# fsr_array.net
KiCad netlist of a schematic drawn in EAGLE
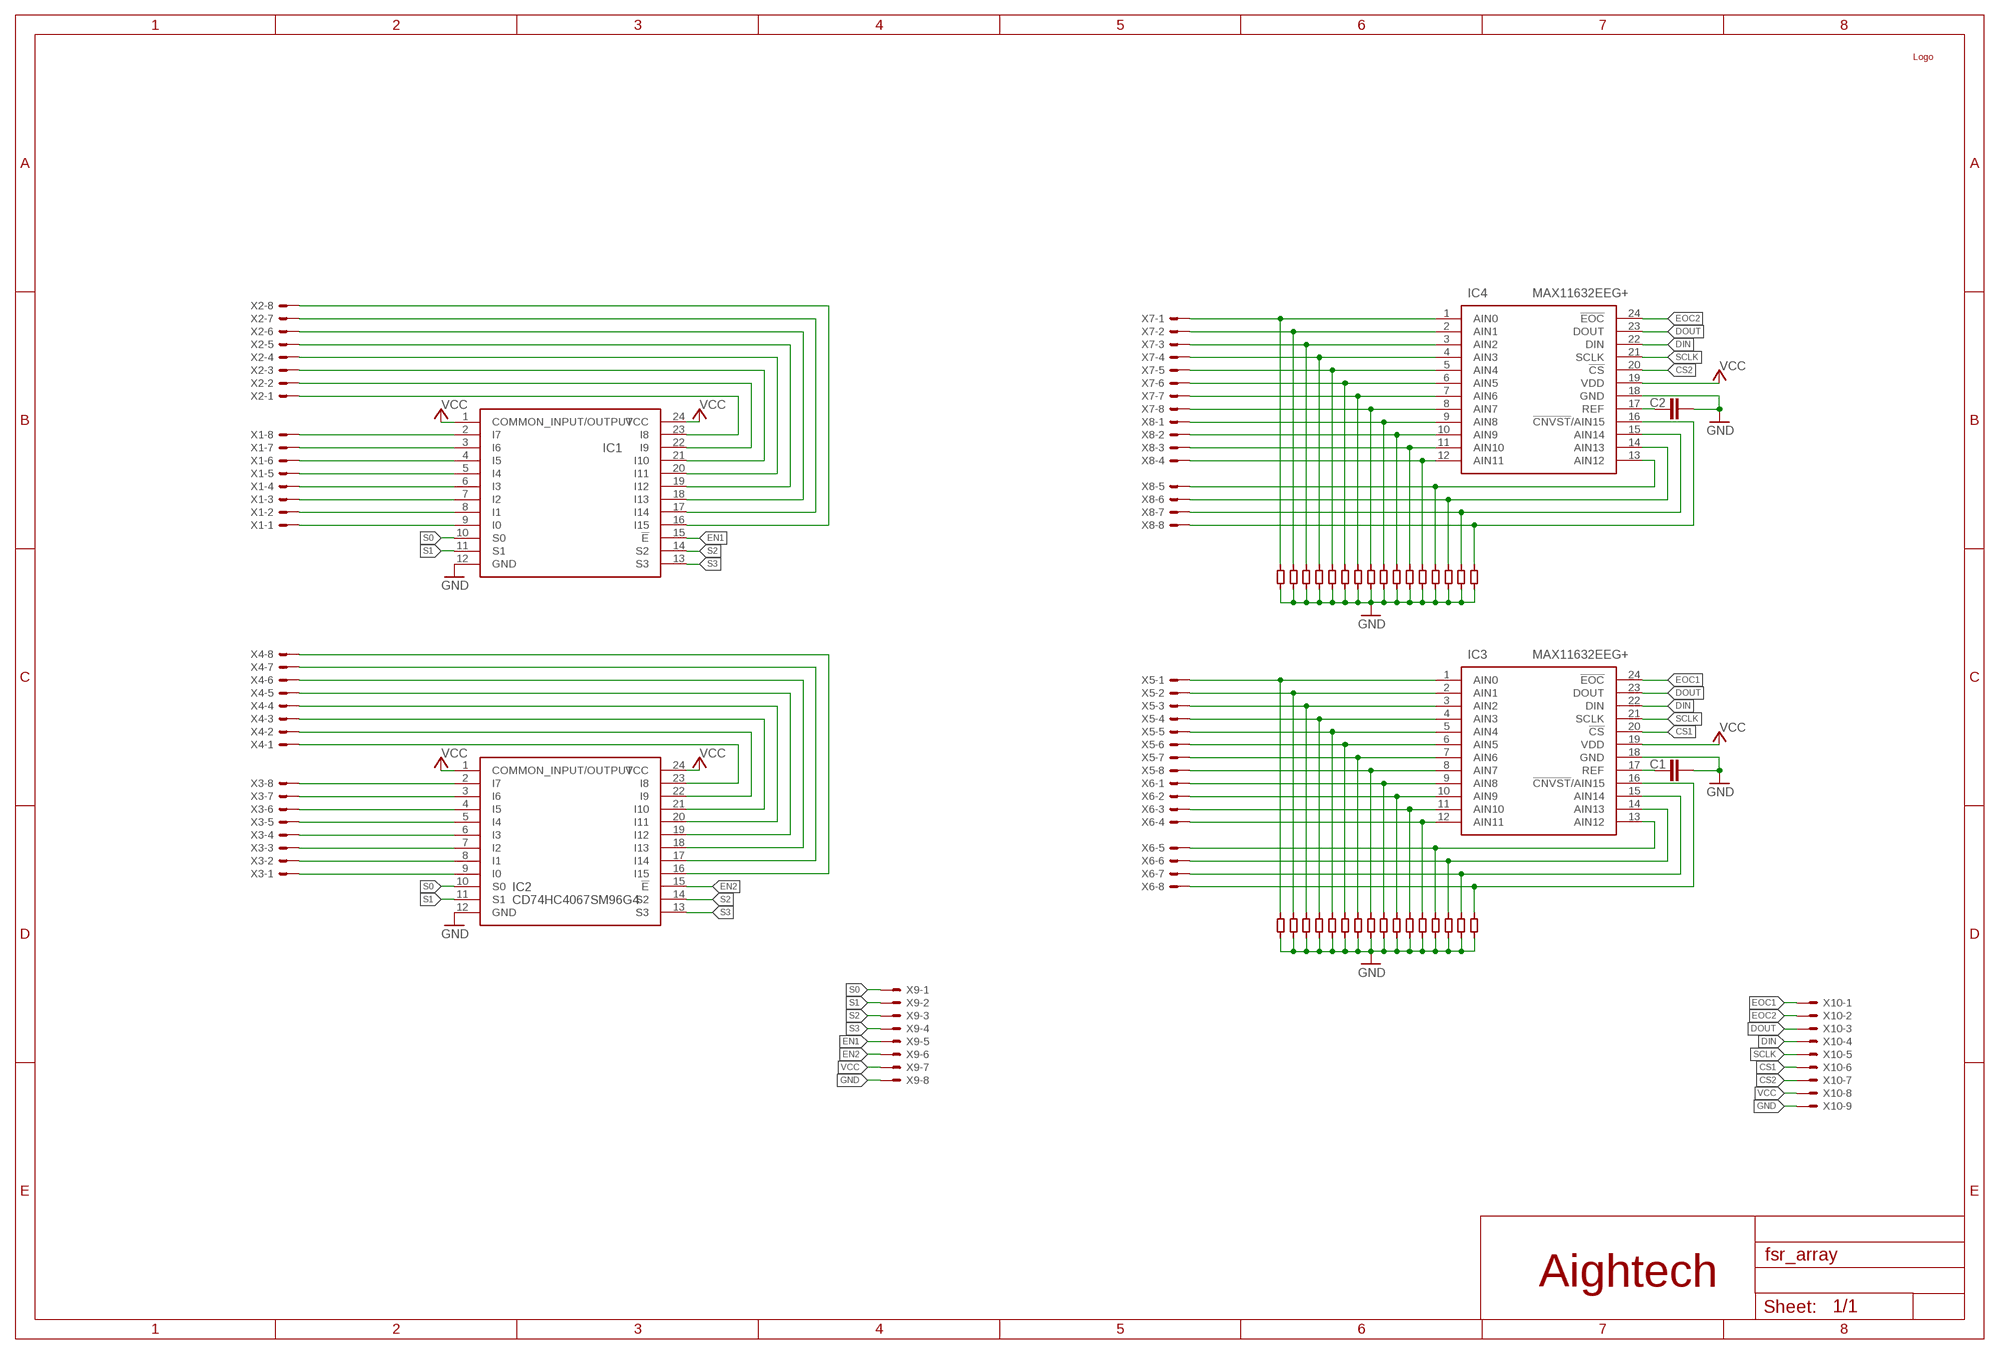
[diagram p0: schematic, sheet 1]

(export (version "E")
  (design (tool "Eeschema 10.0.6"))
  (components
    (comp (ref "C1")
      (value "C-EUC0603")
      (footprint "eagle-import:C0603")
      (libsource (lib "eagle-import") (part "C-EUC0603"))
    )
    (comp (ref "C2")
      (value "C-EUC0603")
      (footprint "eagle-import:C0603")
      (libsource (lib "eagle-import") (part "C-EUC0603"))
    )
    (comp (ref "CPLX1")
      (value "LOGO")
      (footprint "eagle-import:LOGO")
      (libsource (lib "eagle-import") (part "LOGO"))
    )
    (comp (ref "IC1")
      (value "CD74HC4067SM96G4")
      (footprint "eagle-import:SOP65P780X200-24N")
      (libsource (lib "eagle-import") (part "CD74HC4067SM96G4"))
    )
    (comp (ref "IC2")
      (value "CD74HC4067SM96G4")
      (footprint "eagle-import:SOP65P780X200-24N")
      (libsource (lib "eagle-import") (part "CD74HC4067SM96G4"))
    )
    (comp (ref "IC3")
      (value "MAX11632EEG+")
      (footprint "eagle-import:SOP64P602X175-24N")
      (fields (field (name "RS_PART_NUMBER") "1916838"))
      (libsource (lib "eagle-import") (part "MAX11632EEG+"))
    )
    (comp (ref "IC4")
      (value "MAX11632EEG+")
      (footprint "eagle-import:SOP64P602X175-24N")
      (fields (field (name "RS_PART_NUMBER") "1916838"))
      (libsource (lib "eagle-import") (part "MAX11632EEG+"))
    )
    (comp (ref "U$1")
      (value "HALF_RES")
      (footprint "eagle-import:HALP_RES")
      (libsource (lib "eagle-import") (part "HALF_RES"))
    )
    (comp (ref "U$2")
      (value "HALF_RES")
      (footprint "eagle-import:HALP_RES")
      (libsource (lib "eagle-import") (part "HALF_RES"))
    )
    (comp (ref "U$3")
      (value "HALF_RES")
      (footprint "eagle-import:HALP_RES")
      (libsource (lib "eagle-import") (part "HALF_RES"))
    )
    (comp (ref "U$4")
      (value "HALF_RES")
      (footprint "eagle-import:HALP_RES")
      (libsource (lib "eagle-import") (part "HALF_RES"))
    )
    (comp (ref "U$5")
      (value "HALF_RES")
      (footprint "eagle-import:HALP_RES")
      (libsource (lib "eagle-import") (part "HALF_RES"))
    )
    (comp (ref "U$6")
      (value "HALF_RES")
      (footprint "eagle-import:HALP_RES")
      (libsource (lib "eagle-import") (part "HALF_RES"))
    )
    (comp (ref "U$7")
      (value "HALF_RES")
      (footprint "eagle-import:HALP_RES")
      (libsource (lib "eagle-import") (part "HALF_RES"))
    )
    (comp (ref "U$8")
      (value "HALF_RES")
      (footprint "eagle-import:HALP_RES")
      (libsource (lib "eagle-import") (part "HALF_RES"))
    )
    (comp (ref "U$9")
      (value "HALF_RES")
      (footprint "eagle-import:HALP_RES")
      (libsource (lib "eagle-import") (part "HALF_RES"))
    )
    (comp (ref "U$10")
      (value "HALF_RES")
      (footprint "eagle-import:HALP_RES")
      (libsource (lib "eagle-import") (part "HALF_RES"))
    )
    (comp (ref "U$11")
      (value "HALF_RES")
      (footprint "eagle-import:HALP_RES")
      (libsource (lib "eagle-import") (part "HALF_RES"))
    )
    (comp (ref "U$12")
      (value "HALF_RES")
      (footprint "eagle-import:HALP_RES")
      (libsource (lib "eagle-import") (part "HALF_RES"))
    )
    (comp (ref "U$13")
      (value "HALF_RES")
      (footprint "eagle-import:HALP_RES")
      (libsource (lib "eagle-import") (part "HALF_RES"))
    )
    (comp (ref "U$14")
      (value "HALF_RES")
      (footprint "eagle-import:HALP_RES")
      (libsource (lib "eagle-import") (part "HALF_RES"))
    )
    (comp (ref "U$15")
      (value "HALF_RES")
      (footprint "eagle-import:HALP_RES")
      (libsource (lib "eagle-import") (part "HALF_RES"))
    )
    (comp (ref "U$16")
      (value "HALF_RES")
      (footprint "eagle-import:HALP_RES")
      (libsource (lib "eagle-import") (part "HALF_RES"))
    )
    (comp (ref "U$17")
      (value "HALF_RES")
      (footprint "eagle-import:HALP_RES")
      (libsource (lib "eagle-import") (part "HALF_RES"))
    )
    (comp (ref "U$18")
      (value "HALF_RES")
      (footprint "eagle-import:HALP_RES")
      (libsource (lib "eagle-import") (part "HALF_RES"))
    )
    (comp (ref "U$19")
      (value "HALF_RES")
      (footprint "eagle-import:HALP_RES")
      (libsource (lib "eagle-import") (part "HALF_RES"))
    )
    (comp (ref "U$20")
      (value "HALF_RES")
      (footprint "eagle-import:HALP_RES")
      (libsource (lib "eagle-import") (part "HALF_RES"))
    )
    (comp (ref "U$21")
      (value "HALF_RES")
      (footprint "eagle-import:HALP_RES")
      (libsource (lib "eagle-import") (part "HALF_RES"))
    )
    (comp (ref "U$22")
      (value "HALF_RES")
      (footprint "eagle-import:HALP_RES")
      (libsource (lib "eagle-import") (part "HALF_RES"))
    )
    (comp (ref "U$23")
      (value "HALF_RES")
      (footprint "eagle-import:HALP_RES")
      (libsource (lib "eagle-import") (part "HALF_RES"))
    )
    (comp (ref "U$24")
      (value "HALF_RES")
      (footprint "eagle-import:HALP_RES")
      (libsource (lib "eagle-import") (part "HALF_RES"))
    )
    (comp (ref "U$25")
      (value "HALF_RES")
      (footprint "eagle-import:HALP_RES")
      (libsource (lib "eagle-import") (part "HALF_RES"))
    )
    (comp (ref "U$26")
      (value "HALF_RES")
      (footprint "eagle-import:HALP_RES")
      (libsource (lib "eagle-import") (part "HALF_RES"))
    )
    (comp (ref "U$27")
      (value "HALF_RES")
      (footprint "eagle-import:HALP_RES")
      (libsource (lib "eagle-import") (part "HALF_RES"))
    )
    (comp (ref "U$28")
      (value "HALF_RES")
      (footprint "eagle-import:HALP_RES")
      (libsource (lib "eagle-import") (part "HALF_RES"))
    )
    (comp (ref "U$29")
      (value "HALF_RES")
      (footprint "eagle-import:HALP_RES")
      (libsource (lib "eagle-import") (part "HALF_RES"))
    )
    (comp (ref "U$30")
      (value "HALF_RES")
      (footprint "eagle-import:HALP_RES")
      (libsource (lib "eagle-import") (part "HALF_RES"))
    )
    (comp (ref "U$31")
      (value "HALF_RES")
      (footprint "eagle-import:HALP_RES")
      (libsource (lib "eagle-import") (part "HALF_RES"))
    )
    (comp (ref "U$32")
      (value "HALF_RES")
      (footprint "eagle-import:HALP_RES")
      (libsource (lib "eagle-import") (part "HALF_RES"))
    )
    (comp (ref "U$33")
      (value "HALF_RES")
      (footprint "eagle-import:HALP_RES")
      (libsource (lib "eagle-import") (part "HALF_RES"))
    )
    (comp (ref "U$34")
      (value "HALF_RES")
      (footprint "eagle-import:HALP_RES")
      (libsource (lib "eagle-import") (part "HALF_RES"))
    )
    (comp (ref "U$35")
      (value "HALF_RES")
      (footprint "eagle-import:HALP_RES")
      (libsource (lib "eagle-import") (part "HALF_RES"))
    )
    (comp (ref "U$36")
      (value "HALF_RES")
      (footprint "eagle-import:HALP_RES")
      (libsource (lib "eagle-import") (part "HALF_RES"))
    )
    (comp (ref "U$37")
      (value "HALF_RES")
      (footprint "eagle-import:HALP_RES")
      (libsource (lib "eagle-import") (part "HALF_RES"))
    )
    (comp (ref "U$38")
      (value "HALF_RES")
      (footprint "eagle-import:HALP_RES")
      (libsource (lib "eagle-import") (part "HALF_RES"))
    )
    (comp (ref "U$39")
      (value "HALF_RES")
      (footprint "eagle-import:HALP_RES")
      (libsource (lib "eagle-import") (part "HALF_RES"))
    )
    (comp (ref "U$40")
      (value "HALF_RES")
      (footprint "eagle-import:HALP_RES")
      (libsource (lib "eagle-import") (part "HALF_RES"))
    )
    (comp (ref "U$41")
      (value "HALF_RES")
      (footprint "eagle-import:HALP_RES")
      (libsource (lib "eagle-import") (part "HALF_RES"))
    )
    (comp (ref "U$42")
      (value "HALF_RES")
      (footprint "eagle-import:HALP_RES")
      (libsource (lib "eagle-import") (part "HALF_RES"))
    )
    (comp (ref "U$43")
      (value "HALF_RES")
      (footprint "eagle-import:HALP_RES")
      (libsource (lib "eagle-import") (part "HALF_RES"))
    )
    (comp (ref "U$44")
      (value "HALF_RES")
      (footprint "eagle-import:HALP_RES")
      (libsource (lib "eagle-import") (part "HALF_RES"))
    )
    (comp (ref "U$45")
      (value "HALF_RES")
      (footprint "eagle-import:HALP_RES")
      (libsource (lib "eagle-import") (part "HALF_RES"))
    )
    (comp (ref "U$46")
      (value "HALF_RES")
      (footprint "eagle-import:HALP_RES")
      (libsource (lib "eagle-import") (part "HALF_RES"))
    )
    (comp (ref "U$47")
      (value "HALF_RES")
      (footprint "eagle-import:HALP_RES")
      (libsource (lib "eagle-import") (part "HALF_RES"))
    )
    (comp (ref "U$48")
      (value "HALF_RES")
      (footprint "eagle-import:HALP_RES")
      (libsource (lib "eagle-import") (part "HALF_RES"))
    )
    (comp (ref "U$49")
      (value "HALF_RES")
      (footprint "eagle-import:HALP_RES")
      (libsource (lib "eagle-import") (part "HALF_RES"))
    )
    (comp (ref "U$50")
      (value "HALF_RES")
      (footprint "eagle-import:HALP_RES")
      (libsource (lib "eagle-import") (part "HALF_RES"))
    )
    (comp (ref "U$51")
      (value "HALF_RES")
      (footprint "eagle-import:HALP_RES")
      (libsource (lib "eagle-import") (part "HALF_RES"))
    )
    (comp (ref "U$52")
      (value "HALF_RES")
      (footprint "eagle-import:HALP_RES")
      (libsource (lib "eagle-import") (part "HALF_RES"))
    )
    (comp (ref "U$53")
      (value "HALF_RES")
      (footprint "eagle-import:HALP_RES")
      (libsource (lib "eagle-import") (part "HALF_RES"))
    )
    (comp (ref "U$54")
      (value "HALF_RES")
      (footprint "eagle-import:HALP_RES")
      (libsource (lib "eagle-import") (part "HALF_RES"))
    )
    (comp (ref "U$55")
      (value "HALF_RES")
      (footprint "eagle-import:HALP_RES")
      (libsource (lib "eagle-import") (part "HALF_RES"))
    )
    (comp (ref "U$56")
      (value "HALF_RES")
      (footprint "eagle-import:HALP_RES")
      (libsource (lib "eagle-import") (part "HALF_RES"))
    )
    (comp (ref "U$57")
      (value "HALF_RES")
      (footprint "eagle-import:HALP_RES")
      (libsource (lib "eagle-import") (part "HALF_RES"))
    )
    (comp (ref "U$58")
      (value "HALF_RES")
      (footprint "eagle-import:HALP_RES")
      (libsource (lib "eagle-import") (part "HALF_RES"))
    )
    (comp (ref "U$59")
      (value "HALF_RES")
      (footprint "eagle-import:HALP_RES")
      (libsource (lib "eagle-import") (part "HALF_RES"))
    )
    (comp (ref "U$60")
      (value "HALF_RES")
      (footprint "eagle-import:HALP_RES")
      (libsource (lib "eagle-import") (part "HALF_RES"))
    )
    (comp (ref "U$61")
      (value "HALF_RES")
      (footprint "eagle-import:HALP_RES")
      (libsource (lib "eagle-import") (part "HALF_RES"))
    )
    (comp (ref "U$62")
      (value "HALF_RES")
      (footprint "eagle-import:HALP_RES")
      (libsource (lib "eagle-import") (part "HALF_RES"))
    )
    (comp (ref "U$63")
      (value "HALF_RES")
      (footprint "eagle-import:HALP_RES")
      (libsource (lib "eagle-import") (part "HALF_RES"))
    )
    (comp (ref "U$64")
      (value "HALF_RES")
      (footprint "eagle-import:HALP_RES")
      (libsource (lib "eagle-import") (part "HALF_RES"))
    )
    (comp (ref "X1")
      (value "22-23-2081")
      (footprint "eagle-import:22-23-2081")
      (fields (field (name "MF") "MOLEX"))
      (libsource (lib "eagle-import") (part "22-23-2081"))
    )
    (comp (ref "X2")
      (value "22-23-2081")
      (footprint "eagle-import:22-23-2081")
      (fields (field (name "MF") "MOLEX"))
      (libsource (lib "eagle-import") (part "22-23-2081"))
    )
    (comp (ref "X3")
      (value "22-23-2081")
      (footprint "eagle-import:22-23-2081")
      (fields (field (name "MF") "MOLEX"))
      (libsource (lib "eagle-import") (part "22-23-2081"))
    )
    (comp (ref "X4")
      (value "22-23-2081")
      (footprint "eagle-import:22-23-2081")
      (fields (field (name "MF") "MOLEX"))
      (libsource (lib "eagle-import") (part "22-23-2081"))
    )
    (comp (ref "X5")
      (value "22-23-2081")
      (footprint "eagle-import:22-23-2081")
      (fields (field (name "MF") "MOLEX"))
      (libsource (lib "eagle-import") (part "22-23-2081"))
    )
    (comp (ref "X6")
      (value "22-23-2081")
      (footprint "eagle-import:22-23-2081")
      (fields (field (name "MF") "MOLEX"))
      (libsource (lib "eagle-import") (part "22-23-2081"))
    )
    (comp (ref "X7")
      (value "22-23-2081")
      (footprint "eagle-import:22-23-2081")
      (fields (field (name "MF") "MOLEX"))
      (libsource (lib "eagle-import") (part "22-23-2081"))
    )
    (comp (ref "X8")
      (value "22-23-2081")
      (footprint "eagle-import:22-23-2081")
      (fields (field (name "MF") "MOLEX"))
      (libsource (lib "eagle-import") (part "22-23-2081"))
    )
    (comp (ref "X9")
      (value "22-23-2081")
      (footprint "eagle-import:22-23-2081")
      (fields (field (name "MF") "MOLEX"))
      (libsource (lib "eagle-import") (part "22-23-2081"))
    )
    (comp (ref "X10")
      (value "22-23-2091")
      (footprint "eagle-import:22-23-2091")
      (fields (field (name "MF") "MOLEX"))
      (libsource (lib "eagle-import") (part "22-23-2091"))
    )
  )
  (nets
    (net (code "1") (name "CS1") (class "Default")
      (node (ref "IC3") (pin "20") (pinfunction "~{CS}_20") (pintype "bidirectional"))
      (node (ref "X10") (pin "6") (pinfunction "S_6") (pintype "passive"))
    )
    (net (code "2") (name "CS2") (class "Default")
      (node (ref "IC4") (pin "20") (pinfunction "~{CS}_20") (pintype "bidirectional"))
      (node (ref "X10") (pin "7") (pinfunction "S_7") (pintype "passive"))
    )
    (net (code "3") (name "DIN") (class "Default")
      (node (ref "IC3") (pin "22") (pinfunction "DIN_22") (pintype "bidirectional"))
      (node (ref "IC4") (pin "22") (pinfunction "DIN_22") (pintype "bidirectional"))
      (node (ref "X10") (pin "4") (pinfunction "S_4") (pintype "passive"))
    )
    (net (code "4") (name "DOUT") (class "Default")
      (node (ref "IC3") (pin "23") (pinfunction "DOUT_23") (pintype "bidirectional"))
      (node (ref "IC4") (pin "23") (pinfunction "DOUT_23") (pintype "bidirectional"))
      (node (ref "X10") (pin "3") (pinfunction "S_3") (pintype "passive"))
    )
    (net (code "5") (name "EN1") (class "Default")
      (node (ref "IC1") (pin "15") (pinfunction "~{E}_15") (pintype "bidirectional"))
      (node (ref "X9") (pin "5") (pinfunction "S_5") (pintype "passive"))
    )
    (net (code "6") (name "EN2") (class "Default")
      (node (ref "IC2") (pin "15") (pinfunction "~{E}_15") (pintype "bidirectional"))
      (node (ref "X9") (pin "6") (pinfunction "S_6") (pintype "passive"))
    )
    (net (code "7") (name "EOC1") (class "Default")
      (node (ref "IC3") (pin "24") (pinfunction "~{EOC}_24") (pintype "bidirectional"))
      (node (ref "X10") (pin "1") (pinfunction "S_1") (pintype "passive"))
    )
    (net (code "8") (name "EOC2") (class "Default")
      (node (ref "IC4") (pin "24") (pinfunction "~{EOC}_24") (pintype "bidirectional"))
      (node (ref "X10") (pin "2") (pinfunction "S_2") (pintype "passive"))
    )
    (net (code "9") (name "GND") (class "Default")
      (node (ref "C1") (pin "2") (pinfunction "2_2") (pintype "passive"))
      (node (ref "C2") (pin "2") (pinfunction "2_2") (pintype "passive"))
      (node (ref "IC1") (pin "12") (pinfunction "GND_12") (pintype "bidirectional"))
      (node (ref "IC2") (pin "12") (pinfunction "GND_12") (pintype "bidirectional"))
      (node (ref "IC3") (pin "18") (pinfunction "GND_18") (pintype "bidirectional"))
      (node (ref "IC4") (pin "18") (pinfunction "GND_18") (pintype "bidirectional"))
      (node (ref "U$1") (pin "P$1") (pinfunction "P$1_P$1") (pintype "bidirectional"))
      (node (ref "U$11") (pin "P$1") (pinfunction "P$1_P$1") (pintype "bidirectional"))
      (node (ref "U$13") (pin "P$1") (pinfunction "P$1_P$1") (pintype "bidirectional"))
      (node (ref "U$15") (pin "P$1") (pinfunction "P$1_P$1") (pintype "bidirectional"))
      (node (ref "U$17") (pin "P$1") (pinfunction "P$1_P$1") (pintype "bidirectional"))
      (node (ref "U$19") (pin "P$1") (pinfunction "P$1_P$1") (pintype "bidirectional"))
      (node (ref "U$21") (pin "P$1") (pinfunction "P$1_P$1") (pintype "bidirectional"))
      (node (ref "U$23") (pin "P$1") (pinfunction "P$1_P$1") (pintype "bidirectional"))
      (node (ref "U$25") (pin "P$1") (pinfunction "P$1_P$1") (pintype "bidirectional"))
      (node (ref "U$27") (pin "P$1") (pinfunction "P$1_P$1") (pintype "bidirectional"))
      (node (ref "U$29") (pin "P$1") (pinfunction "P$1_P$1") (pintype "bidirectional"))
      (node (ref "U$3") (pin "P$1") (pinfunction "P$1_P$1") (pintype "bidirectional"))
      (node (ref "U$31") (pin "P$1") (pinfunction "P$1_P$1") (pintype "bidirectional"))
      (node (ref "U$33") (pin "P$1") (pinfunction "P$1_P$1") (pintype "bidirectional"))
      (node (ref "U$35") (pin "P$1") (pinfunction "P$1_P$1") (pintype "bidirectional"))
      (node (ref "U$37") (pin "P$1") (pinfunction "P$1_P$1") (pintype "bidirectional"))
      (node (ref "U$39") (pin "P$1") (pinfunction "P$1_P$1") (pintype "bidirectional"))
      (node (ref "U$41") (pin "P$1") (pinfunction "P$1_P$1") (pintype "bidirectional"))
      (node (ref "U$43") (pin "P$1") (pinfunction "P$1_P$1") (pintype "bidirectional"))
      (node (ref "U$45") (pin "P$1") (pinfunction "P$1_P$1") (pintype "bidirectional"))
      (node (ref "U$47") (pin "P$1") (pinfunction "P$1_P$1") (pintype "bidirectional"))
      (node (ref "U$49") (pin "P$1") (pinfunction "P$1_P$1") (pintype "bidirectional"))
      (node (ref "U$5") (pin "P$1") (pinfunction "P$1_P$1") (pintype "bidirectional"))
      (node (ref "U$51") (pin "P$1") (pinfunction "P$1_P$1") (pintype "bidirectional"))
      (node (ref "U$53") (pin "P$1") (pinfunction "P$1_P$1") (pintype "bidirectional"))
      (node (ref "U$55") (pin "P$1") (pinfunction "P$1_P$1") (pintype "bidirectional"))
      (node (ref "U$57") (pin "P$1") (pinfunction "P$1_P$1") (pintype "bidirectional"))
      (node (ref "U$59") (pin "P$1") (pinfunction "P$1_P$1") (pintype "bidirectional"))
      (node (ref "U$61") (pin "P$1") (pinfunction "P$1_P$1") (pintype "bidirectional"))
      (node (ref "U$63") (pin "P$1") (pinfunction "P$1_P$1") (pintype "bidirectional"))
      (node (ref "U$7") (pin "P$1") (pinfunction "P$1_P$1") (pintype "bidirectional"))
      (node (ref "U$9") (pin "P$1") (pinfunction "P$1_P$1") (pintype "bidirectional"))
      (node (ref "X10") (pin "9") (pinfunction "S_9") (pintype "passive"))
      (node (ref "X9") (pin "8") (pinfunction "S_8") (pintype "passive"))
    )
    (net (code "10") (name "Net-(IC1-I0)") (class "Default")
      (node (ref "IC1") (pin "9") (pinfunction "I0_9") (pintype "bidirectional"))
      (node (ref "X1") (pin "1") (pinfunction "S_1") (pintype "passive"))
    )
    (net (code "11") (name "Net-(IC1-I1)") (class "Default")
      (node (ref "IC1") (pin "8") (pinfunction "I1_8") (pintype "bidirectional"))
      (node (ref "X1") (pin "2") (pinfunction "S_2") (pintype "passive"))
    )
    (net (code "12") (name "Net-(IC1-I2)") (class "Default")
      (node (ref "IC1") (pin "7") (pinfunction "I2_7") (pintype "bidirectional"))
      (node (ref "X1") (pin "3") (pinfunction "S_3") (pintype "passive"))
    )
    (net (code "13") (name "Net-(IC1-I3)") (class "Default")
      (node (ref "IC1") (pin "6") (pinfunction "I3_6") (pintype "bidirectional"))
      (node (ref "X1") (pin "4") (pinfunction "S_4") (pintype "passive"))
    )
    (net (code "14") (name "Net-(IC1-I4)") (class "Default")
      (node (ref "IC1") (pin "5") (pinfunction "I4_5") (pintype "bidirectional"))
      (node (ref "X1") (pin "5") (pinfunction "S_5") (pintype "passive"))
    )
    (net (code "15") (name "Net-(IC1-I5)") (class "Default")
      (node (ref "IC1") (pin "4") (pinfunction "I5_4") (pintype "bidirectional"))
      (node (ref "X1") (pin "6") (pinfunction "S_6") (pintype "passive"))
    )
    (net (code "16") (name "Net-(IC1-I6)") (class "Default")
      (node (ref "IC1") (pin "3") (pinfunction "I6_3") (pintype "bidirectional"))
      (node (ref "X1") (pin "7") (pinfunction "S_7") (pintype "passive"))
    )
    (net (code "17") (name "Net-(IC1-I7)") (class "Default")
      (node (ref "IC1") (pin "2") (pinfunction "I7_2") (pintype "bidirectional"))
      (node (ref "X1") (pin "8") (pinfunction "S_8") (pintype "passive"))
    )
    (net (code "18") (name "Net-(IC1-I8)") (class "Default")
      (node (ref "IC1") (pin "23") (pinfunction "I8_23") (pintype "bidirectional"))
      (node (ref "X2") (pin "1") (pinfunction "S_1") (pintype "passive"))
    )
    (net (code "19") (name "Net-(IC1-I9)") (class "Default")
      (node (ref "IC1") (pin "22") (pinfunction "I9_22") (pintype "bidirectional"))
      (node (ref "X2") (pin "2") (pinfunction "S_2") (pintype "passive"))
    )
    (net (code "20") (name "Net-(IC1-I10)") (class "Default")
      (node (ref "IC1") (pin "21") (pinfunction "I10_21") (pintype "bidirectional"))
      (node (ref "X2") (pin "3") (pinfunction "S_3") (pintype "passive"))
    )
    (net (code "21") (name "Net-(IC1-I11)") (class "Default")
      (node (ref "IC1") (pin "20") (pinfunction "I11_20") (pintype "bidirectional"))
      (node (ref "X2") (pin "4") (pinfunction "S_4") (pintype "passive"))
    )
    (net (code "22") (name "Net-(IC1-I12)") (class "Default")
      (node (ref "IC1") (pin "19") (pinfunction "I12_19") (pintype "bidirectional"))
      (node (ref "X2") (pin "5") (pinfunction "S_5") (pintype "passive"))
    )
    (net (code "23") (name "Net-(IC1-I13)") (class "Default")
      (node (ref "IC1") (pin "18") (pinfunction "I13_18") (pintype "bidirectional"))
      (node (ref "X2") (pin "6") (pinfunction "S_6") (pintype "passive"))
    )
    (net (code "24") (name "Net-(IC1-I14)") (class "Default")
      (node (ref "IC1") (pin "17") (pinfunction "I14_17") (pintype "bidirectional"))
      (node (ref "X2") (pin "7") (pinfunction "S_7") (pintype "passive"))
    )
    (net (code "25") (name "Net-(IC1-I15)") (class "Default")
      (node (ref "IC1") (pin "16") (pinfunction "I15_16") (pintype "bidirectional"))
      (node (ref "X2") (pin "8") (pinfunction "S_8") (pintype "passive"))
    )
    (net (code "26") (name "Net-(IC2-I0)") (class "Default")
      (node (ref "IC2") (pin "9") (pinfunction "I0_9") (pintype "bidirectional"))
      (node (ref "X3") (pin "1") (pinfunction "S_1") (pintype "passive"))
    )
    (net (code "27") (name "Net-(IC2-I1)") (class "Default")
      (node (ref "IC2") (pin "8") (pinfunction "I1_8") (pintype "bidirectional"))
      (node (ref "X3") (pin "2") (pinfunction "S_2") (pintype "passive"))
    )
    (net (code "28") (name "Net-(IC2-I2)") (class "Default")
      (node (ref "IC2") (pin "7") (pinfunction "I2_7") (pintype "bidirectional"))
      (node (ref "X3") (pin "3") (pinfunction "S_3") (pintype "passive"))
    )
    (net (code "29") (name "Net-(IC2-I3)") (class "Default")
      (node (ref "IC2") (pin "6") (pinfunction "I3_6") (pintype "bidirectional"))
      (node (ref "X3") (pin "4") (pinfunction "S_4") (pintype "passive"))
    )
    (net (code "30") (name "Net-(IC2-I4)") (class "Default")
      (node (ref "IC2") (pin "5") (pinfunction "I4_5") (pintype "bidirectional"))
      (node (ref "X3") (pin "5") (pinfunction "S_5") (pintype "passive"))
    )
    (net (code "31") (name "Net-(IC2-I5)") (class "Default")
      (node (ref "IC2") (pin "4") (pinfunction "I5_4") (pintype "bidirectional"))
      (node (ref "X3") (pin "6") (pinfunction "S_6") (pintype "passive"))
    )
    (net (code "32") (name "Net-(IC2-I6)") (class "Default")
      (node (ref "IC2") (pin "3") (pinfunction "I6_3") (pintype "bidirectional"))
      (node (ref "X3") (pin "7") (pinfunction "S_7") (pintype "passive"))
    )
    (net (code "33") (name "Net-(IC2-I7)") (class "Default")
      (node (ref "IC2") (pin "2") (pinfunction "I7_2") (pintype "bidirectional"))
      (node (ref "X3") (pin "8") (pinfunction "S_8") (pintype "passive"))
    )
    (net (code "34") (name "Net-(IC2-I8)") (class "Default")
      (node (ref "IC2") (pin "23") (pinfunction "I8_23") (pintype "bidirectional"))
      (node (ref "X4") (pin "1") (pinfunction "S_1") (pintype "passive"))
    )
    (net (code "35") (name "Net-(IC2-I9)") (class "Default")
      (node (ref "IC2") (pin "22") (pinfunction "I9_22") (pintype "bidirectional"))
      (node (ref "X4") (pin "2") (pinfunction "S_2") (pintype "passive"))
    )
    (net (code "36") (name "Net-(IC2-I10)") (class "Default")
      (node (ref "IC2") (pin "21") (pinfunction "I10_21") (pintype "bidirectional"))
      (node (ref "X4") (pin "3") (pinfunction "S_3") (pintype "passive"))
    )
    (net (code "37") (name "Net-(IC2-I11)") (class "Default")
      (node (ref "IC2") (pin "20") (pinfunction "I11_20") (pintype "bidirectional"))
      (node (ref "X4") (pin "4") (pinfunction "S_4") (pintype "passive"))
    )
    (net (code "38") (name "Net-(IC2-I12)") (class "Default")
      (node (ref "IC2") (pin "19") (pinfunction "I12_19") (pintype "bidirectional"))
      (node (ref "X4") (pin "5") (pinfunction "S_5") (pintype "passive"))
    )
    (net (code "39") (name "Net-(IC2-I13)") (class "Default")
      (node (ref "IC2") (pin "18") (pinfunction "I13_18") (pintype "bidirectional"))
      (node (ref "X4") (pin "6") (pinfunction "S_6") (pintype "passive"))
    )
    (net (code "40") (name "Net-(IC2-I14)") (class "Default")
      (node (ref "IC2") (pin "17") (pinfunction "I14_17") (pintype "bidirectional"))
      (node (ref "X4") (pin "7") (pinfunction "S_7") (pintype "passive"))
    )
    (net (code "41") (name "Net-(IC2-I15)") (class "Default")
      (node (ref "IC2") (pin "16") (pinfunction "I15_16") (pintype "bidirectional"))
      (node (ref "X4") (pin "8") (pinfunction "S_8") (pintype "passive"))
    )
    (net (code "42") (name "Net-(IC3-AIN0)") (class "Default")
      (node (ref "IC3") (pin "1") (pinfunction "AIN0_1") (pintype "bidirectional"))
      (node (ref "U$16") (pin "P$1") (pinfunction "P$1_P$1") (pintype "bidirectional"))
      (node (ref "X5") (pin "1") (pinfunction "S_1") (pintype "passive"))
    )
    (net (code "43") (name "Net-(IC3-AIN1)") (class "Default")
      (node (ref "IC3") (pin "2") (pinfunction "AIN1_2") (pintype "bidirectional"))
      (node (ref "U$14") (pin "P$1") (pinfunction "P$1_P$1") (pintype "bidirectional"))
      (node (ref "X5") (pin "2") (pinfunction "S_2") (pintype "passive"))
    )
    (net (code "44") (name "Net-(IC3-AIN2)") (class "Default")
      (node (ref "IC3") (pin "3") (pinfunction "AIN2_3") (pintype "bidirectional"))
      (node (ref "U$12") (pin "P$1") (pinfunction "P$1_P$1") (pintype "bidirectional"))
      (node (ref "X5") (pin "3") (pinfunction "S_3") (pintype "passive"))
    )
    (net (code "45") (name "Net-(IC3-AIN3)") (class "Default")
      (node (ref "IC3") (pin "4") (pinfunction "AIN3_4") (pintype "bidirectional"))
      (node (ref "U$10") (pin "P$1") (pinfunction "P$1_P$1") (pintype "bidirectional"))
      (node (ref "X5") (pin "4") (pinfunction "S_4") (pintype "passive"))
    )
    (net (code "46") (name "Net-(IC3-AIN4)") (class "Default")
      (node (ref "IC3") (pin "5") (pinfunction "AIN4_5") (pintype "bidirectional"))
      (node (ref "U$8") (pin "P$1") (pinfunction "P$1_P$1") (pintype "bidirectional"))
      (node (ref "X5") (pin "5") (pinfunction "S_5") (pintype "passive"))
    )
    (net (code "47") (name "Net-(IC3-AIN5)") (class "Default")
      (node (ref "IC3") (pin "6") (pinfunction "AIN5_6") (pintype "bidirectional"))
      (node (ref "U$6") (pin "P$1") (pinfunction "P$1_P$1") (pintype "bidirectional"))
      (node (ref "X5") (pin "6") (pinfunction "S_6") (pintype "passive"))
    )
    (net (code "48") (name "Net-(IC3-AIN6)") (class "Default")
      (node (ref "IC3") (pin "7") (pinfunction "AIN6_7") (pintype "bidirectional"))
      (node (ref "U$4") (pin "P$1") (pinfunction "P$1_P$1") (pintype "bidirectional"))
      (node (ref "X5") (pin "7") (pinfunction "S_7") (pintype "passive"))
    )
    (net (code "49") (name "Net-(IC3-AIN7)") (class "Default")
      (node (ref "IC3") (pin "8") (pinfunction "AIN7_8") (pintype "bidirectional"))
      (node (ref "U$2") (pin "P$1") (pinfunction "P$1_P$1") (pintype "bidirectional"))
      (node (ref "X5") (pin "8") (pinfunction "S_8") (pintype "passive"))
    )
    (net (code "50") (name "Net-(IC3-AIN8)") (class "Default")
      (node (ref "IC3") (pin "9") (pinfunction "AIN8_9") (pintype "bidirectional"))
      (node (ref "U$32") (pin "P$1") (pinfunction "P$1_P$1") (pintype "bidirectional"))
      (node (ref "X6") (pin "1") (pinfunction "S_1") (pintype "passive"))
    )
    (net (code "51") (name "Net-(IC3-AIN9)") (class "Default")
      (node (ref "IC3") (pin "10") (pinfunction "AIN9_10") (pintype "bidirectional"))
      (node (ref "U$30") (pin "P$1") (pinfunction "P$1_P$1") (pintype "bidirectional"))
      (node (ref "X6") (pin "2") (pinfunction "S_2") (pintype "passive"))
    )
    (net (code "52") (name "Net-(IC3-AIN10)") (class "Default")
      (node (ref "IC3") (pin "11") (pinfunction "AIN10_11") (pintype "bidirectional"))
      (node (ref "U$28") (pin "P$1") (pinfunction "P$1_P$1") (pintype "bidirectional"))
      (node (ref "X6") (pin "3") (pinfunction "S_3") (pintype "passive"))
    )
    (net (code "53") (name "Net-(IC3-AIN11)") (class "Default")
      (node (ref "IC3") (pin "12") (pinfunction "AIN11_12") (pintype "bidirectional"))
      (node (ref "U$26") (pin "P$1") (pinfunction "P$1_P$1") (pintype "bidirectional"))
      (node (ref "X6") (pin "4") (pinfunction "S_4") (pintype "passive"))
    )
    (net (code "54") (name "Net-(IC3-AIN12)") (class "Default")
      (node (ref "IC3") (pin "13") (pinfunction "AIN12_13") (pintype "bidirectional"))
      (node (ref "U$24") (pin "P$1") (pinfunction "P$1_P$1") (pintype "bidirectional"))
      (node (ref "X6") (pin "5") (pinfunction "S_5") (pintype "passive"))
    )
    (net (code "55") (name "Net-(IC3-AIN13)") (class "Default")
      (node (ref "IC3") (pin "14") (pinfunction "AIN13_14") (pintype "bidirectional"))
      (node (ref "U$22") (pin "P$1") (pinfunction "P$1_P$1") (pintype "bidirectional"))
      (node (ref "X6") (pin "6") (pinfunction "S_6") (pintype "passive"))
    )
    (net (code "56") (name "Net-(IC3-AIN14)") (class "Default")
      (node (ref "IC3") (pin "15") (pinfunction "AIN14_15") (pintype "bidirectional"))
      (node (ref "U$20") (pin "P$1") (pinfunction "P$1_P$1") (pintype "bidirectional"))
      (node (ref "X6") (pin "7") (pinfunction "S_7") (pintype "passive"))
    )
    (net (code "57") (name "Net-(IC3-REF)") (class "Default")
      (node (ref "C1") (pin "1") (pinfunction "1_1") (pintype "passive"))
      (node (ref "IC3") (pin "17") (pinfunction "REF_17") (pintype "bidirectional"))
    )
    (net (code "58") (name "Net-(IC3-~{CNVST}{slash}AIN15)") (class "Default")
      (node (ref "IC3") (pin "16") (pinfunction "~{CNVST}/AIN15_16") (pintype "bidirectional"))
      (node (ref "U$18") (pin "P$1") (pinfunction "P$1_P$1") (pintype "bidirectional"))
      (node (ref "X6") (pin "8") (pinfunction "S_8") (pintype "passive"))
    )
    (net (code "59") (name "Net-(IC4-AIN0)") (class "Default")
      (node (ref "IC4") (pin "1") (pinfunction "AIN0_1") (pintype "bidirectional"))
      (node (ref "U$48") (pin "P$1") (pinfunction "P$1_P$1") (pintype "bidirectional"))
      (node (ref "X7") (pin "1") (pinfunction "S_1") (pintype "passive"))
    )
    (net (code "60") (name "Net-(IC4-AIN1)") (class "Default")
      (node (ref "IC4") (pin "2") (pinfunction "AIN1_2") (pintype "bidirectional"))
      (node (ref "U$46") (pin "P$1") (pinfunction "P$1_P$1") (pintype "bidirectional"))
      (node (ref "X7") (pin "2") (pinfunction "S_2") (pintype "passive"))
    )
    (net (code "61") (name "Net-(IC4-AIN2)") (class "Default")
      (node (ref "IC4") (pin "3") (pinfunction "AIN2_3") (pintype "bidirectional"))
      (node (ref "U$44") (pin "P$1") (pinfunction "P$1_P$1") (pintype "bidirectional"))
      (node (ref "X7") (pin "3") (pinfunction "S_3") (pintype "passive"))
    )
    (net (code "62") (name "Net-(IC4-AIN3)") (class "Default")
      (node (ref "IC4") (pin "4") (pinfunction "AIN3_4") (pintype "bidirectional"))
      (node (ref "U$42") (pin "P$1") (pinfunction "P$1_P$1") (pintype "bidirectional"))
      (node (ref "X7") (pin "4") (pinfunction "S_4") (pintype "passive"))
    )
    (net (code "63") (name "Net-(IC4-AIN4)") (class "Default")
      (node (ref "IC4") (pin "5") (pinfunction "AIN4_5") (pintype "bidirectional"))
      (node (ref "U$40") (pin "P$1") (pinfunction "P$1_P$1") (pintype "bidirectional"))
      (node (ref "X7") (pin "5") (pinfunction "S_5") (pintype "passive"))
    )
    (net (code "64") (name "Net-(IC4-AIN5)") (class "Default")
      (node (ref "IC4") (pin "6") (pinfunction "AIN5_6") (pintype "bidirectional"))
      (node (ref "U$38") (pin "P$1") (pinfunction "P$1_P$1") (pintype "bidirectional"))
      (node (ref "X7") (pin "6") (pinfunction "S_6") (pintype "passive"))
    )
    (net (code "65") (name "Net-(IC4-AIN6)") (class "Default")
      (node (ref "IC4") (pin "7") (pinfunction "AIN6_7") (pintype "bidirectional"))
      (node (ref "U$36") (pin "P$1") (pinfunction "P$1_P$1") (pintype "bidirectional"))
      (node (ref "X7") (pin "7") (pinfunction "S_7") (pintype "passive"))
    )
    (net (code "66") (name "Net-(IC4-AIN7)") (class "Default")
      (node (ref "IC4") (pin "8") (pinfunction "AIN7_8") (pintype "bidirectional"))
      (node (ref "U$34") (pin "P$1") (pinfunction "P$1_P$1") (pintype "bidirectional"))
      (node (ref "X7") (pin "8") (pinfunction "S_8") (pintype "passive"))
    )
    (net (code "67") (name "Net-(IC4-AIN8)") (class "Default")
      (node (ref "IC4") (pin "9") (pinfunction "AIN8_9") (pintype "bidirectional"))
      (node (ref "U$64") (pin "P$1") (pinfunction "P$1_P$1") (pintype "bidirectional"))
      (node (ref "X8") (pin "1") (pinfunction "S_1") (pintype "passive"))
    )
    (net (code "68") (name "Net-(IC4-AIN9)") (class "Default")
      (node (ref "IC4") (pin "10") (pinfunction "AIN9_10") (pintype "bidirectional"))
      (node (ref "U$62") (pin "P$1") (pinfunction "P$1_P$1") (pintype "bidirectional"))
      (node (ref "X8") (pin "2") (pinfunction "S_2") (pintype "passive"))
    )
    (net (code "69") (name "Net-(IC4-AIN10)") (class "Default")
      (node (ref "IC4") (pin "11") (pinfunction "AIN10_11") (pintype "bidirectional"))
      (node (ref "U$60") (pin "P$1") (pinfunction "P$1_P$1") (pintype "bidirectional"))
      (node (ref "X8") (pin "3") (pinfunction "S_3") (pintype "passive"))
    )
    (net (code "70") (name "Net-(IC4-AIN11)") (class "Default")
      (node (ref "IC4") (pin "12") (pinfunction "AIN11_12") (pintype "bidirectional"))
      (node (ref "U$58") (pin "P$1") (pinfunction "P$1_P$1") (pintype "bidirectional"))
      (node (ref "X8") (pin "4") (pinfunction "S_4") (pintype "passive"))
    )
    (net (code "71") (name "Net-(IC4-AIN12)") (class "Default")
      (node (ref "IC4") (pin "13") (pinfunction "AIN12_13") (pintype "bidirectional"))
      (node (ref "U$56") (pin "P$1") (pinfunction "P$1_P$1") (pintype "bidirectional"))
      (node (ref "X8") (pin "5") (pinfunction "S_5") (pintype "passive"))
    )
    (net (code "72") (name "Net-(IC4-AIN13)") (class "Default")
      (node (ref "IC4") (pin "14") (pinfunction "AIN13_14") (pintype "bidirectional"))
      (node (ref "U$54") (pin "P$1") (pinfunction "P$1_P$1") (pintype "bidirectional"))
      (node (ref "X8") (pin "6") (pinfunction "S_6") (pintype "passive"))
    )
    (net (code "73") (name "Net-(IC4-AIN14)") (class "Default")
      (node (ref "IC4") (pin "15") (pinfunction "AIN14_15") (pintype "bidirectional"))
      (node (ref "U$52") (pin "P$1") (pinfunction "P$1_P$1") (pintype "bidirectional"))
      (node (ref "X8") (pin "7") (pinfunction "S_7") (pintype "passive"))
    )
    (net (code "74") (name "Net-(IC4-REF)") (class "Default")
      (node (ref "C2") (pin "1") (pinfunction "1_1") (pintype "passive"))
      (node (ref "IC4") (pin "17") (pinfunction "REF_17") (pintype "bidirectional"))
    )
    (net (code "75") (name "Net-(IC4-~{CNVST}{slash}AIN15)") (class "Default")
      (node (ref "IC4") (pin "16") (pinfunction "~{CNVST}/AIN15_16") (pintype "bidirectional"))
      (node (ref "U$50") (pin "P$1") (pinfunction "P$1_P$1") (pintype "bidirectional"))
      (node (ref "X8") (pin "8") (pinfunction "S_8") (pintype "passive"))
    )
    (net (code "76") (name "S0") (class "Default")
      (node (ref "IC1") (pin "10") (pinfunction "S0_10") (pintype "bidirectional"))
      (node (ref "IC2") (pin "10") (pinfunction "S0_10") (pintype "bidirectional"))
      (node (ref "X9") (pin "1") (pinfunction "S_1") (pintype "passive"))
    )
    (net (code "77") (name "S1") (class "Default")
      (node (ref "IC1") (pin "11") (pinfunction "S1_11") (pintype "bidirectional"))
      (node (ref "IC2") (pin "11") (pinfunction "S1_11") (pintype "bidirectional"))
      (node (ref "X9") (pin "2") (pinfunction "S_2") (pintype "passive"))
    )
    (net (code "78") (name "S2") (class "Default")
      (node (ref "IC1") (pin "14") (pinfunction "S2_14") (pintype "bidirectional"))
      (node (ref "IC2") (pin "14") (pinfunction "S2_14") (pintype "bidirectional"))
      (node (ref "X9") (pin "3") (pinfunction "S_3") (pintype "passive"))
    )
    (net (code "79") (name "S3") (class "Default")
      (node (ref "IC1") (pin "13") (pinfunction "S3_13") (pintype "bidirectional"))
      (node (ref "IC2") (pin "13") (pinfunction "S3_13") (pintype "bidirectional"))
      (node (ref "X9") (pin "4") (pinfunction "S_4") (pintype "passive"))
    )
    (net (code "80") (name "SCLK") (class "Default")
      (node (ref "IC3") (pin "21") (pinfunction "SCLK_21") (pintype "bidirectional"))
      (node (ref "IC4") (pin "21") (pinfunction "SCLK_21") (pintype "bidirectional"))
      (node (ref "X10") (pin "5") (pinfunction "S_5") (pintype "passive"))
    )
    (net (code "81") (name "VCC") (class "Default")
      (node (ref "IC1") (pin "1") (pinfunction "COMMON_INPUT/OUTPUT_1") (pintype "bidirectional"))
      (node (ref "IC1") (pin "24") (pinfunction "VCC_24") (pintype "bidirectional"))
      (node (ref "IC2") (pin "1") (pinfunction "COMMON_INPUT/OUTPUT_1") (pintype "bidirectional"))
      (node (ref "IC2") (pin "24") (pinfunction "VCC_24") (pintype "bidirectional"))
      (node (ref "IC3") (pin "19") (pinfunction "VDD_19") (pintype "bidirectional"))
      (node (ref "IC4") (pin "19") (pinfunction "VDD_19") (pintype "bidirectional"))
      (node (ref "X10") (pin "8") (pinfunction "S_8") (pintype "passive"))
      (node (ref "X9") (pin "7") (pinfunction "S_7") (pintype "passive"))
    )
  )
)
